# 3Ph_FWR.net
KiCad netlist of a schematic drawn in EAGLE
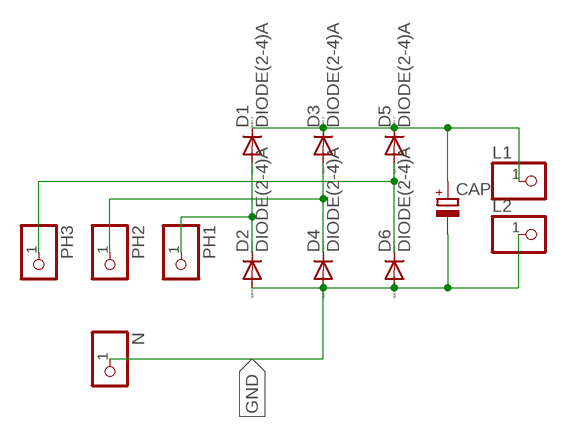
[diagram p0: schematic, sheet 1]

(export (version "E")
  (design (tool "Eeschema 10.0.6"))
  (components
    (comp (ref "CAP")
      (value "CAP_POL")
      (footprint "eagle-import:E3,5-8")
      (libsource (lib "eagle-import") (part "CAP_POL"))
    )
    (comp (ref "D1")
      (value "DIODE(2-4)A")
      (footprint "eagle-import:DO35-10")
      (libsource (lib "eagle-import") (part "DIODE(2-4)A"))
    )
    (comp (ref "D2")
      (value "DIODE(2-4)A")
      (footprint "eagle-import:DO35-10")
      (libsource (lib "eagle-import") (part "DIODE(2-4)A"))
    )
    (comp (ref "D3")
      (value "DIODE(2-4)A")
      (footprint "eagle-import:DO35-10")
      (libsource (lib "eagle-import") (part "DIODE(2-4)A"))
    )
    (comp (ref "D4")
      (value "DIODE(2-4)A")
      (footprint "eagle-import:DO35-10")
      (libsource (lib "eagle-import") (part "DIODE(2-4)A"))
    )
    (comp (ref "D5")
      (value "DIODE(2-4)A")
      (footprint "eagle-import:DO35-10")
      (libsource (lib "eagle-import") (part "DIODE(2-4)A"))
    )
    (comp (ref "D6")
      (value "DIODE(2-4)A")
      (footprint "eagle-import:DO35-10")
      (libsource (lib "eagle-import") (part "DIODE(2-4)A"))
    )
    (comp (ref "L1")
      (value "PINHD-1X1")
      (footprint "eagle-import:1X01")
      (libsource (lib "eagle-import") (part "PINHD-1X1"))
    )
    (comp (ref "L2")
      (value "PINHD-1X1")
      (footprint "eagle-import:1X01")
      (libsource (lib "eagle-import") (part "PINHD-1X1"))
    )
    (comp (ref "N")
      (value "PINHD-1X1")
      (footprint "eagle-import:1X01")
      (libsource (lib "eagle-import") (part "PINHD-1X1"))
    )
    (comp (ref "PH1")
      (value "PINHD-1X1")
      (footprint "eagle-import:1X01")
      (libsource (lib "eagle-import") (part "PINHD-1X1"))
    )
    (comp (ref "PH2")
      (value "PINHD-1X1")
      (footprint "eagle-import:1X01")
      (libsource (lib "eagle-import") (part "PINHD-1X1"))
    )
    (comp (ref "PH3")
      (value "PINHD-1X1")
      (footprint "eagle-import:1X01")
      (libsource (lib "eagle-import") (part "PINHD-1X1"))
    )
  )
  (nets
    (net (code "1") (name "GND") (class "Default")
      (node (ref "CAP") (pin "-") (pinfunction "-_-") (pintype "passive"))
      (node (ref "D2") (pin "A") (pinfunction "A_A") (pintype "passive"))
      (node (ref "D4") (pin "A") (pinfunction "A_A") (pintype "passive"))
      (node (ref "D6") (pin "A") (pinfunction "A_A") (pintype "passive"))
      (node (ref "L2") (pin "1") (pinfunction "1_1") (pintype "passive"))
      (node (ref "N") (pin "1") (pinfunction "1_1") (pintype "passive"))
    )
    (net (code "2") (name "Net-(CAP-Pad+)") (class "Default")
      (node (ref "CAP") (pin "+") (pinfunction "+_+") (pintype "passive"))
      (node (ref "D1") (pin "C") (pinfunction "C_C") (pintype "passive"))
      (node (ref "D3") (pin "C") (pinfunction "C_C") (pintype "passive"))
      (node (ref "D5") (pin "C") (pinfunction "C_C") (pintype "passive"))
      (node (ref "L1") (pin "1") (pinfunction "1_1") (pintype "passive"))
    )
    (net (code "3") (name "Net-(D1-PadA)") (class "Default")
      (node (ref "D1") (pin "A") (pinfunction "A_A") (pintype "passive"))
      (node (ref "D2") (pin "C") (pinfunction "C_C") (pintype "passive"))
      (node (ref "PH1") (pin "1") (pinfunction "1_1") (pintype "passive"))
    )
    (net (code "4") (name "Net-(D3-PadA)") (class "Default")
      (node (ref "D3") (pin "A") (pinfunction "A_A") (pintype "passive"))
      (node (ref "D4") (pin "C") (pinfunction "C_C") (pintype "passive"))
      (node (ref "PH2") (pin "1") (pinfunction "1_1") (pintype "passive"))
    )
    (net (code "5") (name "Net-(D5-PadA)") (class "Default")
      (node (ref "D5") (pin "A") (pinfunction "A_A") (pintype "passive"))
      (node (ref "D6") (pin "C") (pinfunction "C_C") (pintype "passive"))
      (node (ref "PH3") (pin "1") (pinfunction "1_1") (pintype "passive"))
    )
  )
)
